# ME4Driver.net
KiCad netlist of a schematic drawn in EasyEDA Pro
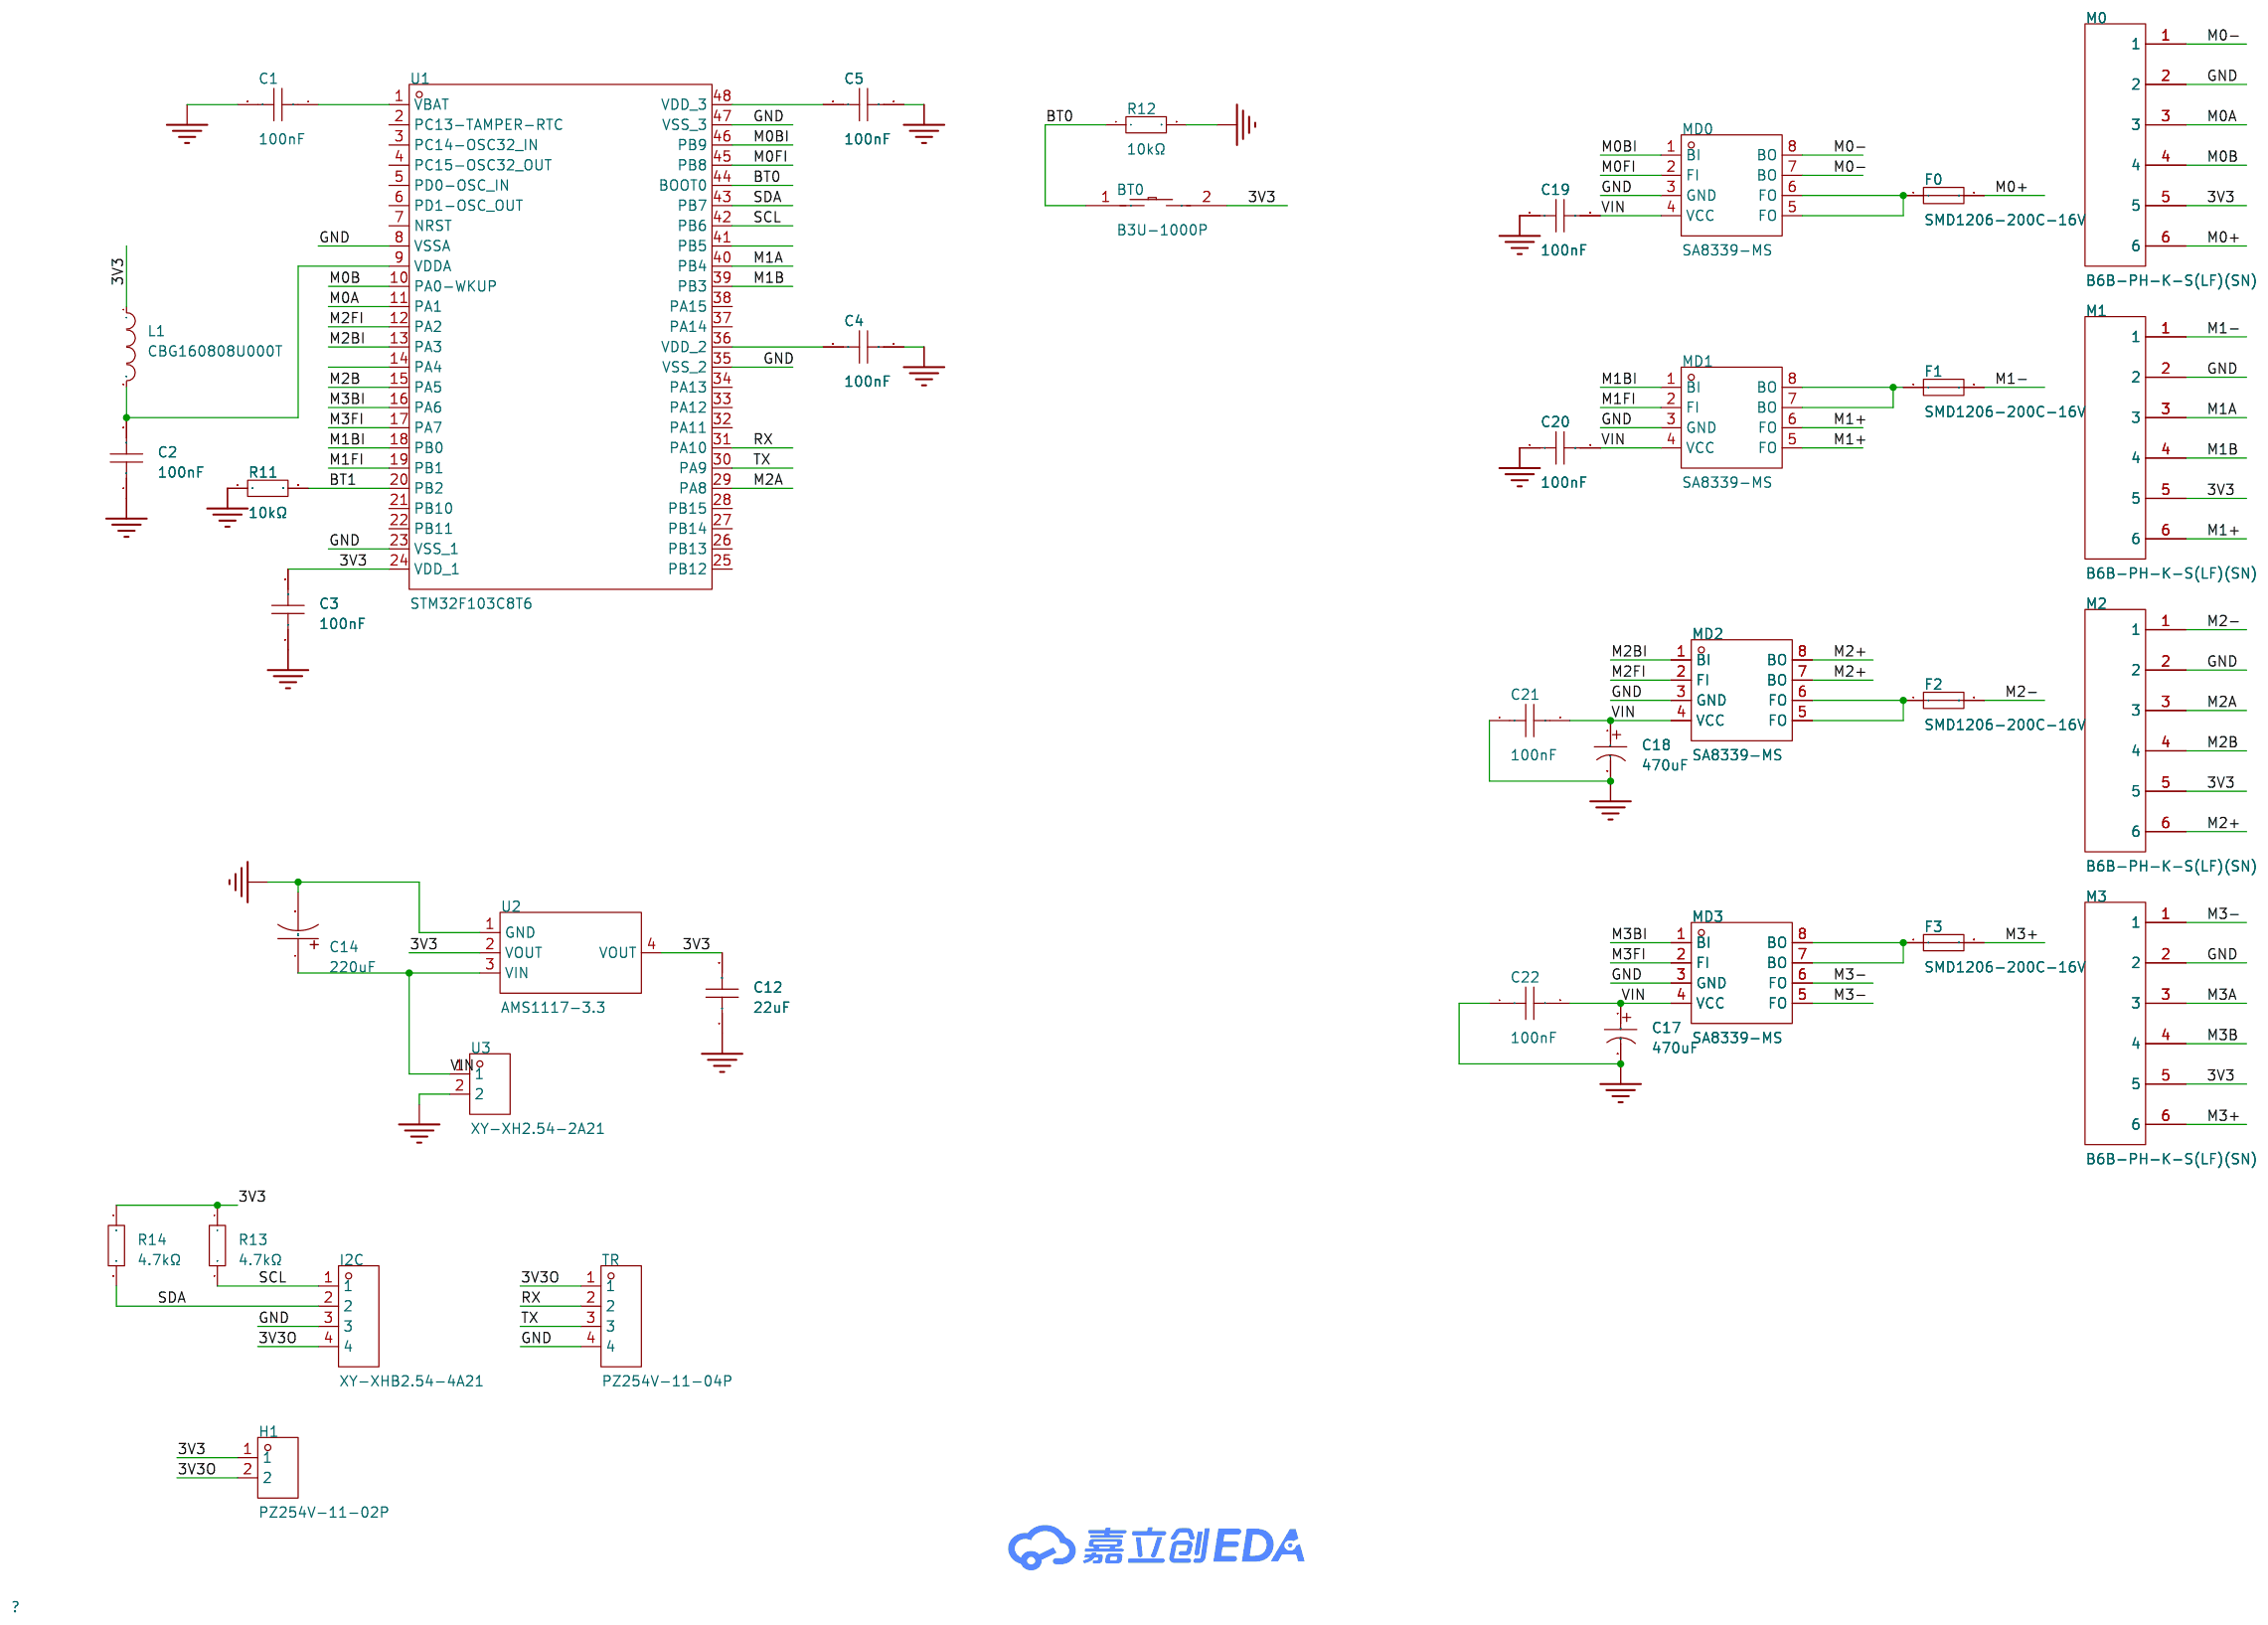
[diagram p0: schematic sheet]

(export (version "E")
  (design (tool "Eeschema 10.0.6"))
  (components
    (comp (ref "BT0")
      (value "B3U-1000P")
      (footprint "easyedapro:KEY-SMD_B3U-1000PM")
      (fields (field (name "Manufacturer") "OMRON(欧姆龙)"))
      (libsource (lib "easyedapro") (part "B3U-1000P"))
    )
    (comp (ref "C1")
      (value "100nF")
      (footprint "easyedapro:C0603")
      (description "容值:100nF;精度:±10%;额定电压:50V;材质(温度系数):X7R;")
      (fields
        (field (name "Manufacturer Part") "CGA0603X7R104K500JT")
        (field (name "Manufacturer") "HRE(芯声)")
      )
      (libsource (lib "easyedapro") (part "CGA0603X7R104K500JT"))
    )
    (comp (ref "C2")
      (value "100nF")
      (footprint "easyedapro:C0603")
      (description "容值:100nF;精度:±10%;额定电压:50V;材质(温度系数):X7R;")
      (fields
        (field (name "Manufacturer Part") "CGA0603X7R104K500JT")
        (field (name "Manufacturer") "HRE(芯声)")
      )
      (libsource (lib "easyedapro") (part "CGA0603X7R104K500JT"))
    )
    (comp (ref "C3")
      (value "100nF")
      (footprint "easyedapro:C0603")
      (description "容值:100nF;精度:±10%;额定电压:50V;材质(温度系数):X7R;")
      (fields
        (field (name "Manufacturer Part") "CGA0603X7R104K500JT")
        (field (name "Manufacturer") "HRE(芯声)")
      )
      (libsource (lib "easyedapro") (part "CGA0603X7R104K500JT"))
    )
    (comp (ref "C4")
      (value "100nF")
      (footprint "easyedapro:C0603")
      (description "容值:100nF;精度:±10%;额定电压:50V;材质(温度系数):X7R;")
      (fields
        (field (name "Manufacturer Part") "CGA0603X7R104K500JT")
        (field (name "Manufacturer") "HRE(芯声)")
      )
      (libsource (lib "easyedapro") (part "CGA0603X7R104K500JT"))
    )
    (comp (ref "C5")
      (value "100nF")
      (footprint "easyedapro:C0603")
      (description "容值:100nF;精度:±10%;额定电压:50V;材质(温度系数):X7R;")
      (fields
        (field (name "Manufacturer Part") "CGA0603X7R104K500JT")
        (field (name "Manufacturer") "HRE(芯声)")
      )
      (libsource (lib "easyedapro") (part "CGA0603X7R104K500JT"))
    )
    (comp (ref "C12")
      (value "22uF")
      (footprint "easyedapro:C0603")
      (description "容值:100nF;精度:±10%;额定电压:50V;材质(温度系数):X7R;")
      (fields (field (name "Manufacturer Part") "TAJA226K010RNJ") (field (name "Manufacturer") "Kyocera AVX"))
      (libsource (lib "easyedapro") (part "CGA0603X7R104K500JT"))
    )
    (comp (ref "C14")
      (value "220uF")
      (footprint "easyedapro:CAP-SMD_BD6.3-L6.6-W6.6-FD")
      (description "容值:220uF;精度:±20%;额定电压:16V;纹波电流:-;等效串联电阻:-;")
      (fields (field (name "Manufacturer Part") "VT1C221M-CRE77") (field (name "Manufacturer") "VT(首科)"))
      (libsource (lib "easyedapro") (part "VT1C221M-CRE77"))
    )
    (comp (ref "C17")
      (value "470uF")
      (footprint "easyedapro:CAP-TH_BD8.0-P3.50-D0.6-FD")
      (description "容值:220uF;精度:±20%;额定电压:35V;纹波电流:-;等效串联电阻:-;")
      (fields (field (name "Manufacturer Part") "KF471M025F115A") (field (name "Manufacturer") "CapXon(丰宾)"))
      (libsource (lib "easyedapro") (part "220uf/35V"))
    )
    (comp (ref "C18")
      (value "470uF")
      (footprint "easyedapro:CAP-TH_BD8.0-P3.50-D0.6-FD")
      (description "容值:220uF;精度:±20%;额定电压:35V;纹波电流:-;等效串联电阻:-;")
      (fields (field (name "Manufacturer Part") "KF471M025F115A") (field (name "Manufacturer") "CapXon(丰宾)"))
      (libsource (lib "easyedapro") (part "220uf/35V"))
    )
    (comp (ref "C19")
      (value "100nF")
      (footprint "easyedapro:C0603")
      (description "容值:100nF;精度:±10%;额定电压:50V;材质(温度系数):X7R;")
      (fields
        (field (name "Manufacturer Part") "CGA0603X7R104K500JT")
        (field (name "Manufacturer") "HRE(芯声)")
      )
      (libsource (lib "easyedapro") (part "CGA0603X7R104K500JT"))
    )
    (comp (ref "C20")
      (value "100nF")
      (footprint "easyedapro:C0603")
      (description "容值:100nF;精度:±10%;额定电压:50V;材质(温度系数):X7R;")
      (fields
        (field (name "Manufacturer Part") "CGA0603X7R104K500JT")
        (field (name "Manufacturer") "HRE(芯声)")
      )
      (libsource (lib "easyedapro") (part "CGA0603X7R104K500JT"))
    )
    (comp (ref "C21")
      (value "100nF")
      (footprint "easyedapro:C0603")
      (description "容值:100nF;精度:±10%;额定电压:50V;材质(温度系数):X7R;")
      (fields
        (field (name "Manufacturer Part") "CGA0603X7R104K500JT")
        (field (name "Manufacturer") "HRE(芯声)")
      )
      (libsource (lib "easyedapro") (part "CGA0603X7R104K500JT"))
    )
    (comp (ref "C22")
      (value "100nF")
      (footprint "easyedapro:C0603")
      (description "容值:100nF;精度:±10%;额定电压:50V;材质(温度系数):X7R;")
      (fields
        (field (name "Manufacturer Part") "CGA0603X7R104K500JT")
        (field (name "Manufacturer") "HRE(芯声)")
      )
      (libsource (lib "easyedapro") (part "CGA0603X7R104K500JT"))
    )
    (comp (ref "F0")
      (value "SMD1206-200C-16V")
      (footprint "easyedapro:F1812")
      (description "最大电压:16V;最大电流:40A;保持电流:3A;跳闸电流:6A;")
      (fields (field (name "Manufacturer") "BNstar(比诺星)"))
      (libsource (lib "easyedapro") (part "BSMD1812-300-16V"))
    )
    (comp (ref "F1")
      (value "SMD1206-200C-16V")
      (footprint "easyedapro:F1812")
      (description "最大电压:16V;最大电流:40A;保持电流:3A;跳闸电流:6A;")
      (fields (field (name "Manufacturer") "BNstar(比诺星)"))
      (libsource (lib "easyedapro") (part "BSMD1812-300-16V"))
    )
    (comp (ref "F2")
      (value "SMD1206-200C-16V")
      (footprint "easyedapro:F1812")
      (description "最大电压:16V;最大电流:40A;保持电流:3A;跳闸电流:6A;")
      (fields (field (name "Manufacturer") "BNstar(比诺星)"))
      (libsource (lib "easyedapro") (part "BSMD1812-300-16V"))
    )
    (comp (ref "F3")
      (value "SMD1206-200C-16V")
      (footprint "easyedapro:F1812")
      (description "最大电压:16V;最大电流:40A;保持电流:3A;跳闸电流:6A;")
      (fields (field (name "Manufacturer") "BNstar(比诺星)"))
      (libsource (lib "easyedapro") (part "BSMD1812-300-16V"))
    )
    (comp (ref "H1")
      (value "PZ254V-11-02P")
      (footprint "easyedapro:HDR-TH_2P-P2.54-V-M")
      (fields (field (name "Manufacturer") "XFCN(兴飞)"))
      (libsource (lib "easyedapro") (part "PZ254V-11-02P"))
    )
    (comp (ref "I2C")
      (value "XY-XHB2.54-4A21")
      (footprint "easyedapro:HDR-TH_4P-P2.50-H-F-W7.3-N")
      (description "插针结构:1x4P;间距:2.54mm;安装方式:弯插;总PIN数:4P;排数:1;每排PIN数:4;行距:2.54mm;额定电流:2A;工作温度范围:-25°C~+85°C;")
      (fields (field (name "Manufacturer") "XYECONN(辛译)"))
      (libsource (lib "easyedapro") (part "XY-XHB2.54-4A21"))
    )
    (comp (ref "L1")
      (value "CBG160808U000T")
      (footprint "easyedapro:L0603")
      (description "标称阻抗@测试频率:0Ω@100MHz;直流电阻(RDC):100mΩ;")
      (fields (field (name "Manufacturer") "FH(风华)"))
      (libsource (lib "easyedapro") (part "CBG160808U000T"))
    )
    (comp (ref "M0")
      (value "B6B-PH-K-S(LF)(SN)")
      (footprint "easyedapro:CONN-TH_B6B-PH-K-S")
      (fields (field (name "Manufacturer") "JST"))
      (libsource (lib "easyedapro") (part "B6B-PH-K-S(LF)(SN)"))
    )
    (comp (ref "M1")
      (value "B6B-PH-K-S(LF)(SN)")
      (footprint "easyedapro:CONN-TH_B6B-PH-K-S")
      (fields (field (name "Manufacturer") "JST"))
      (libsource (lib "easyedapro") (part "B6B-PH-K-S(LF)(SN)"))
    )
    (comp (ref "M2")
      (value "B6B-PH-K-S(LF)(SN)")
      (footprint "easyedapro:CONN-TH_B6B-PH-K-S")
      (fields (field (name "Manufacturer") "JST"))
      (libsource (lib "easyedapro") (part "B6B-PH-K-S(LF)(SN)"))
    )
    (comp (ref "M3")
      (value "B6B-PH-K-S(LF)(SN)")
      (footprint "easyedapro:CONN-TH_B6B-PH-K-S")
      (fields (field (name "Manufacturer") "JST"))
      (libsource (lib "easyedapro") (part "B6B-PH-K-S(LF)(SN)"))
    )
    (comp (ref "MD0")
      (value "SA8339-MS")
      (footprint "easyedapro:SOP-8_L4.9-W3.9-P1.27-LS6.0-BL")
      (fields (field (name "Manufacturer") "MSKSEMI(美森科)"))
      (libsource (lib "easyedapro") (part "SA8339-MS"))
    )
    (comp (ref "MD1")
      (value "SA8339-MS")
      (footprint "easyedapro:SOP-8_L4.9-W3.9-P1.27-LS6.0-BL")
      (fields (field (name "Manufacturer") "MSKSEMI(美森科)"))
      (libsource (lib "easyedapro") (part "SA8339-MS"))
    )
    (comp (ref "MD2")
      (value "SA8339-MS")
      (footprint "easyedapro:SOP-8_L4.9-W3.9-P1.27-LS6.0-BL")
      (fields (field (name "Manufacturer") "MSKSEMI(美森科)"))
      (libsource (lib "easyedapro") (part "SA8339-MS"))
    )
    (comp (ref "MD3")
      (value "SA8339-MS")
      (footprint "easyedapro:SOP-8_L4.9-W3.9-P1.27-LS6.0-BL")
      (fields (field (name "Manufacturer") "MSKSEMI(美森科)"))
      (libsource (lib "easyedapro") (part "SA8339-MS"))
    )
    (comp (ref "R11")
      (value "10kΩ")
      (fields
        (field (name "Manufacturer Part") "0603WAF1002T5E")
        (field (name "Manufacturer") "UNI-ROYAL(厚声)")
      )
      (libsource (lib "easyedapro") (part "电阻"))
    )
    (comp (ref "R12")
      (value "10kΩ")
      (fields
        (field (name "Manufacturer Part") "0603WAF1002T5E")
        (field (name "Manufacturer") "UNI-ROYAL(厚声)")
      )
      (libsource (lib "easyedapro") (part "电阻"))
    )
    (comp (ref "R13")
      (value "4.7kΩ")
      (footprint "easyedapro:R1206")
      (description "电阻类型:厚膜电阻;阻值:4.7kΩ;精度:±1%;功率:250mW;最大工作电压:200V;温度系数:±100ppm/°C;")
      (fields
        (field (name "Manufacturer Part") "1206W4F4701T5E")
        (field (name "Manufacturer") "UNI-ROYAL(厚声)")
      )
      (libsource (lib "easyedapro") (part "1206W4F4701T5E"))
    )
    (comp (ref "R14")
      (value "4.7kΩ")
      (footprint "easyedapro:R1206")
      (description "电阻类型:厚膜电阻;阻值:4.7kΩ;精度:±1%;功率:250mW;最大工作电压:200V;温度系数:±100ppm/°C;")
      (fields
        (field (name "Manufacturer Part") "1206W4F4701T5E")
        (field (name "Manufacturer") "UNI-ROYAL(厚声)")
      )
      (libsource (lib "easyedapro") (part "1206W4F4701T5E"))
    )
    (comp (ref "TR")
      (value "PZ254V-11-04P")
      (footprint "easyedapro:HDR-TH_4P-P2.54-V-M")
      (fields (field (name "Manufacturer") "XFCN(兴飞)"))
      (libsource (lib "easyedapro") (part "PZ254V-11-04P_C2691448"))
    )
    (comp (ref "U1")
      (value "STM32F103C8T6")
      (footprint "easyedapro:LQFP-48_L7.0-W7.0-P0.50-LS9.0-BL")
      (description "CPU内核:ARM-M3;CPU最大主频:72MHz;应用领域:-;")
      (fields (field (name "Manufacturer") "ST(意法半导体)"))
      (libsource (lib "easyedapro") (part "STM32F103C8T6"))
    )
    (comp (ref "U2")
      (value "AMS1117-3.3")
      (footprint "easyedapro:SOT-223-3_L6.5-W3.4-P2.30-LS7.0-BR")
      (description "输出类型:固定;工作电压:-;输出电压:3.3V;输出电流:1A;电源纹波抑制比(PSRR):72dB@(120Hz);输出极性:正极;")
      (fields (field (name "Manufacturer") "AMS"))
      (libsource (lib "easyedapro") (part "AMS1117-3.3"))
    )
    (comp (ref "U3")
      (value "XY-XH2.54-2A21")
      (footprint "easyedapro:HDR-TH_2P-P2.50_XY-XH2.54-2A21")
      (description "插针结构:1x2P;间距:2.54mm;安装方式:弯插;总PIN数:2P;排数:1;每排PIN数:2;行距:2.54mm;额定电流:3A;工作温度范围:-25°C~+85°C;")
      (fields (field (name "Manufacturer") "XYECONN(辛译)"))
      (libsource (lib "easyedapro") (part "XY-XH2.54-2A21"))
    )
  )
  (nets
    (net (code "1") (name "/3V3") (class "Default")
      (node (ref "BT0") (pin "2") (pinfunction "2_2") (pintype "unspecified"))
      (node (ref "C12") (pin "2") (pinfunction "2_2") (pintype "unspecified"))
      (node (ref "C3") (pin "2") (pinfunction "2_2") (pintype "unspecified"))
      (node (ref "H1") (pin "1") (pinfunction "1_1") (pintype "unspecified"))
      (node (ref "L1") (pin "1") (pinfunction "1_1") (pintype "unspecified"))
      (node (ref "M0") (pin "5") (pinfunction "5_5") (pintype "input"))
      (node (ref "M1") (pin "5") (pinfunction "5_5") (pintype "input"))
      (node (ref "M2") (pin "5") (pinfunction "5_5") (pintype "input"))
      (node (ref "M3") (pin "5") (pinfunction "5_5") (pintype "input"))
      (node (ref "R13") (pin "1") (pinfunction "1_1") (pintype "input"))
      (node (ref "R14") (pin "1") (pinfunction "1_1") (pintype "input"))
      (node (ref "U1") (pin "24") (pinfunction "VDD_1_24") (pintype "unspecified"))
      (node (ref "U2") (pin "2") (pinfunction "VOUT_2") (pintype "unspecified"))
      (node (ref "U2") (pin "4") (pinfunction "VOUT_4") (pintype "unspecified"))
    )
    (net (code "2") (name "/3V3O") (class "Default")
      (node (ref "H1") (pin "2") (pinfunction "2_2") (pintype "unspecified"))
      (node (ref "I2C") (pin "4") (pinfunction "4_4") (pintype "unspecified"))
      (node (ref "TR") (pin "1") (pinfunction "1_1") (pintype "unspecified"))
    )
    (net (code "3") (name "/BT0") (class "Default")
      (node (ref "BT0") (pin "1") (pinfunction "1_1") (pintype "unspecified"))
      (node (ref "R12") (pin "1") (pinfunction "1_1") (pintype "input"))
      (node (ref "U1") (pin "44") (pinfunction "BOOT0_44") (pintype "unspecified"))
    )
    (net (code "4") (name "/BT1") (class "Default")
      (node (ref "R11") (pin "2") (pinfunction "2_2") (pintype "input"))
      (node (ref "U1") (pin "20") (pinfunction "PB2_20") (pintype "unspecified"))
    )
    (net (code "5") (name "/M0+") (class "Default")
      (node (ref "F0") (pin "2") (pinfunction "2_2") (pintype "unspecified"))
      (node (ref "M0") (pin "6") (pinfunction "6_6") (pintype "input"))
    )
    (net (code "6") (name "/M0-") (class "Default")
      (node (ref "M0") (pin "1") (pinfunction "1_1") (pintype "input"))
      (node (ref "MD0") (pin "7") (pinfunction "BO_7") (pintype "unspecified"))
      (node (ref "MD0") (pin "8") (pinfunction "BO_8") (pintype "unspecified"))
    )
    (net (code "7") (name "/M0A") (class "Default")
      (node (ref "M0") (pin "3") (pinfunction "3_3") (pintype "input"))
      (node (ref "U1") (pin "11") (pinfunction "PA1_11") (pintype "unspecified"))
    )
    (net (code "8") (name "/M0B") (class "Default")
      (node (ref "M0") (pin "4") (pinfunction "4_4") (pintype "input"))
      (node (ref "U1") (pin "10") (pinfunction "PA0-WKUP_10") (pintype "unspecified"))
    )
    (net (code "9") (name "/M0BI") (class "Default")
      (node (ref "MD0") (pin "1") (pinfunction "BI_1") (pintype "unspecified"))
      (node (ref "U1") (pin "46") (pinfunction "PB9_46") (pintype "unspecified"))
    )
    (net (code "10") (name "/M0FI") (class "Default")
      (node (ref "MD0") (pin "2") (pinfunction "FI_2") (pintype "unspecified"))
      (node (ref "U1") (pin "45") (pinfunction "PB8_45") (pintype "unspecified"))
    )
    (net (code "11") (name "/M1+") (class "Default")
      (node (ref "M1") (pin "6") (pinfunction "6_6") (pintype "input"))
      (node (ref "MD1") (pin "5") (pinfunction "FO_5") (pintype "unspecified"))
      (node (ref "MD1") (pin "6") (pinfunction "FO_6") (pintype "unspecified"))
    )
    (net (code "12") (name "/M1-") (class "Default")
      (node (ref "F1") (pin "2") (pinfunction "2_2") (pintype "unspecified"))
      (node (ref "M1") (pin "1") (pinfunction "1_1") (pintype "input"))
    )
    (net (code "13") (name "/M1A") (class "Default")
      (node (ref "M1") (pin "3") (pinfunction "3_3") (pintype "input"))
      (node (ref "U1") (pin "40") (pinfunction "PB4_40") (pintype "unspecified"))
    )
    (net (code "14") (name "/M1B") (class "Default")
      (node (ref "M1") (pin "4") (pinfunction "4_4") (pintype "input"))
      (node (ref "U1") (pin "39") (pinfunction "PB3_39") (pintype "unspecified"))
    )
    (net (code "15") (name "/M1BI") (class "Default")
      (node (ref "MD1") (pin "1") (pinfunction "BI_1") (pintype "unspecified"))
      (node (ref "U1") (pin "18") (pinfunction "PB0_18") (pintype "unspecified"))
    )
    (net (code "16") (name "/M1FI") (class "Default")
      (node (ref "MD1") (pin "2") (pinfunction "FI_2") (pintype "unspecified"))
      (node (ref "U1") (pin "19") (pinfunction "PB1_19") (pintype "unspecified"))
    )
    (net (code "17") (name "/M2+") (class "Default")
      (node (ref "M2") (pin "6") (pinfunction "6_6") (pintype "input"))
      (node (ref "MD2") (pin "7") (pinfunction "BO_7") (pintype "unspecified"))
      (node (ref "MD2") (pin "8") (pinfunction "BO_8") (pintype "unspecified"))
    )
    (net (code "18") (name "/M2-") (class "Default")
      (node (ref "F2") (pin "2") (pinfunction "2_2") (pintype "unspecified"))
      (node (ref "M2") (pin "1") (pinfunction "1_1") (pintype "input"))
    )
    (net (code "19") (name "/M2A") (class "Default")
      (node (ref "M2") (pin "3") (pinfunction "3_3") (pintype "input"))
      (node (ref "U1") (pin "29") (pinfunction "PA8_29") (pintype "unspecified"))
    )
    (net (code "20") (name "/M2B") (class "Default")
      (node (ref "M2") (pin "4") (pinfunction "4_4") (pintype "input"))
      (node (ref "U1") (pin "15") (pinfunction "PA5_15") (pintype "unspecified"))
    )
    (net (code "21") (name "/M2BI") (class "Default")
      (node (ref "MD2") (pin "1") (pinfunction "BI_1") (pintype "unspecified"))
      (node (ref "U1") (pin "13") (pinfunction "PA3_13") (pintype "unspecified"))
    )
    (net (code "22") (name "/M2FI") (class "Default")
      (node (ref "MD2") (pin "2") (pinfunction "FI_2") (pintype "unspecified"))
      (node (ref "U1") (pin "12") (pinfunction "PA2_12") (pintype "unspecified"))
    )
    (net (code "23") (name "/M3+") (class "Default")
      (node (ref "F3") (pin "2") (pinfunction "2_2") (pintype "unspecified"))
      (node (ref "M3") (pin "6") (pinfunction "6_6") (pintype "input"))
    )
    (net (code "24") (name "/M3-") (class "Default")
      (node (ref "M3") (pin "1") (pinfunction "1_1") (pintype "input"))
      (node (ref "MD3") (pin "5") (pinfunction "FO_5") (pintype "unspecified"))
      (node (ref "MD3") (pin "6") (pinfunction "FO_6") (pintype "unspecified"))
    )
    (net (code "25") (name "/M3A") (class "Default")
      (node (ref "M3") (pin "3") (pinfunction "3_3") (pintype "input"))
    )
    (net (code "26") (name "/M3B") (class "Default")
      (node (ref "M3") (pin "4") (pinfunction "4_4") (pintype "input"))
    )
    (net (code "27") (name "/M3BI") (class "Default")
      (node (ref "MD3") (pin "1") (pinfunction "BI_1") (pintype "unspecified"))
      (node (ref "U1") (pin "16") (pinfunction "PA6_16") (pintype "unspecified"))
    )
    (net (code "28") (name "/M3FI") (class "Default")
      (node (ref "MD3") (pin "2") (pinfunction "FI_2") (pintype "unspecified"))
      (node (ref "U1") (pin "17") (pinfunction "PA7_17") (pintype "unspecified"))
    )
    (net (code "29") (name "/RX") (class "Default")
      (node (ref "TR") (pin "2") (pinfunction "2_2") (pintype "unspecified"))
      (node (ref "U1") (pin "31") (pinfunction "PA10_31") (pintype "unspecified"))
    )
    (net (code "30") (name "/SCL") (class "Default")
      (node (ref "I2C") (pin "1") (pinfunction "1_1") (pintype "unspecified"))
      (node (ref "R13") (pin "2") (pinfunction "2_2") (pintype "input"))
      (node (ref "U1") (pin "42") (pinfunction "PB6_42") (pintype "unspecified"))
    )
    (net (code "31") (name "/SDA") (class "Default")
      (node (ref "I2C") (pin "2") (pinfunction "2_2") (pintype "unspecified"))
      (node (ref "R14") (pin "2") (pinfunction "2_2") (pintype "input"))
      (node (ref "U1") (pin "43") (pinfunction "PB7_43") (pintype "unspecified"))
    )
    (net (code "32") (name "/TX") (class "Default")
      (node (ref "TR") (pin "3") (pinfunction "3_3") (pintype "unspecified"))
      (node (ref "U1") (pin "30") (pinfunction "PA9_30") (pintype "unspecified"))
    )
    (net (code "33") (name "/VIN") (class "Default")
      (node (ref "C14") (pin "1") (pinfunction "1_1") (pintype "unspecified"))
      (node (ref "C17") (pin "1") (pinfunction "1_1") (pintype "input"))
      (node (ref "C18") (pin "1") (pinfunction "1_1") (pintype "input"))
      (node (ref "C19") (pin "2") (pinfunction "2_2") (pintype "unspecified"))
      (node (ref "C20") (pin "2") (pinfunction "2_2") (pintype "unspecified"))
      (node (ref "C21") (pin "2") (pinfunction "2_2") (pintype "unspecified"))
      (node (ref "C22") (pin "2") (pinfunction "2_2") (pintype "unspecified"))
      (node (ref "MD0") (pin "4") (pinfunction "VCC_4") (pintype "unspecified"))
      (node (ref "MD1") (pin "4") (pinfunction "VCC_4") (pintype "unspecified"))
      (node (ref "MD2") (pin "4") (pinfunction "VCC_4") (pintype "unspecified"))
      (node (ref "MD3") (pin "4") (pinfunction "VCC_4") (pintype "unspecified"))
      (node (ref "U2") (pin "3") (pinfunction "VIN_3") (pintype "unspecified"))
      (node (ref "U3") (pin "1") (pinfunction "1_1") (pintype "unspecified"))
    )
    (net (code "34") (name "GND") (class "Default")
      (node (ref "C1") (pin "2") (pinfunction "2_2") (pintype "unspecified"))
      (node (ref "C12") (pin "1") (pinfunction "1_1") (pintype "unspecified"))
      (node (ref "C14") (pin "2") (pinfunction "2_2") (pintype "unspecified"))
      (node (ref "C17") (pin "2") (pinfunction "2_2") (pintype "input"))
      (node (ref "C18") (pin "2") (pinfunction "2_2") (pintype "input"))
      (node (ref "C19") (pin "1") (pinfunction "1_1") (pintype "unspecified"))
      (node (ref "C2") (pin "1") (pinfunction "1_1") (pintype "unspecified"))
      (node (ref "C20") (pin "1") (pinfunction "1_1") (pintype "unspecified"))
      (node (ref "C21") (pin "1") (pinfunction "1_1") (pintype "unspecified"))
      (node (ref "C22") (pin "1") (pinfunction "1_1") (pintype "unspecified"))
      (node (ref "C3") (pin "1") (pinfunction "1_1") (pintype "unspecified"))
      (node (ref "C4") (pin "1") (pinfunction "1_1") (pintype "unspecified"))
      (node (ref "C5") (pin "1") (pinfunction "1_1") (pintype "unspecified"))
      (node (ref "I2C") (pin "3") (pinfunction "3_3") (pintype "unspecified"))
      (node (ref "M0") (pin "2") (pinfunction "2_2") (pintype "input"))
      (node (ref "M1") (pin "2") (pinfunction "2_2") (pintype "input"))
      (node (ref "M2") (pin "2") (pinfunction "2_2") (pintype "input"))
      (node (ref "M3") (pin "2") (pinfunction "2_2") (pintype "input"))
      (node (ref "MD0") (pin "3") (pinfunction "GND_3") (pintype "unspecified"))
      (node (ref "MD1") (pin "3") (pinfunction "GND_3") (pintype "unspecified"))
      (node (ref "MD2") (pin "3") (pinfunction "GND_3") (pintype "unspecified"))
      (node (ref "MD3") (pin "3") (pinfunction "GND_3") (pintype "unspecified"))
      (node (ref "R11") (pin "1") (pinfunction "1_1") (pintype "input"))
      (node (ref "R12") (pin "2") (pinfunction "2_2") (pintype "input"))
      (node (ref "TR") (pin "4") (pinfunction "4_4") (pintype "unspecified"))
      (node (ref "U1") (pin "23") (pinfunction "VSS_1_23") (pintype "unspecified"))
      (node (ref "U1") (pin "35") (pinfunction "VSS_2_35") (pintype "unspecified"))
      (node (ref "U1") (pin "47") (pinfunction "VSS_3_47") (pintype "unspecified"))
      (node (ref "U1") (pin "8") (pinfunction "VSSA_8") (pintype "unspecified"))
      (node (ref "U2") (pin "1") (pinfunction "GND_1") (pintype "unspecified"))
      (node (ref "U3") (pin "2") (pinfunction "2_2") (pintype "unspecified"))
    )
    (net (code "35") (name "Net-(F0-Pad1)") (class "Default")
      (node (ref "F0") (pin "1") (pinfunction "1_1") (pintype "unspecified"))
      (node (ref "MD0") (pin "5") (pinfunction "FO_5") (pintype "unspecified"))
      (node (ref "MD0") (pin "6") (pinfunction "FO_6") (pintype "unspecified"))
    )
    (net (code "36") (name "Net-(F1-Pad1)") (class "Default")
      (node (ref "F1") (pin "1") (pinfunction "1_1") (pintype "unspecified"))
      (node (ref "MD1") (pin "7") (pinfunction "BO_7") (pintype "unspecified"))
      (node (ref "MD1") (pin "8") (pinfunction "BO_8") (pintype "unspecified"))
    )
    (net (code "37") (name "Net-(F2-Pad1)") (class "Default")
      (node (ref "F2") (pin "1") (pinfunction "1_1") (pintype "unspecified"))
      (node (ref "MD2") (pin "5") (pinfunction "FO_5") (pintype "unspecified"))
      (node (ref "MD2") (pin "6") (pinfunction "FO_6") (pintype "unspecified"))
    )
    (net (code "38") (name "Net-(F3-Pad1)") (class "Default")
      (node (ref "F3") (pin "1") (pinfunction "1_1") (pintype "unspecified"))
      (node (ref "MD3") (pin "7") (pinfunction "BO_7") (pintype "unspecified"))
      (node (ref "MD3") (pin "8") (pinfunction "BO_8") (pintype "unspecified"))
    )
    (net (code "39") (name "Net-(U1-VBAT)") (class "Default")
      (node (ref "C1") (pin "1") (pinfunction "1_1") (pintype "unspecified"))
      (node (ref "U1") (pin "1") (pinfunction "VBAT_1") (pintype "unspecified"))
    )
    (net (code "40") (name "Net-(U1-VDDA)") (class "Default")
      (node (ref "C2") (pin "2") (pinfunction "2_2") (pintype "unspecified"))
      (node (ref "L1") (pin "2") (pinfunction "2_2") (pintype "unspecified"))
      (node (ref "U1") (pin "9") (pinfunction "VDDA_9") (pintype "unspecified"))
    )
    (net (code "41") (name "Net-(U1-VDD_2)") (class "Default")
      (node (ref "C4") (pin "2") (pinfunction "2_2") (pintype "unspecified"))
      (node (ref "U1") (pin "36") (pinfunction "VDD_2_36") (pintype "unspecified"))
    )
    (net (code "42") (name "Net-(U1-VDD_3)") (class "Default")
      (node (ref "C5") (pin "2") (pinfunction "2_2") (pintype "unspecified"))
      (node (ref "U1") (pin "48") (pinfunction "VDD_3_48") (pintype "unspecified"))
    )
    (net (code "43") (name "unconnected-(U1-NRST-Pad7)") (class "Default")
      (node (ref "U1") (pin "7") (pinfunction "NRST_7") (pintype "unspecified"))
    )
    (net (code "44") (name "unconnected-(U1-PA4-Pad14)") (class "Default")
      (node (ref "U1") (pin "14") (pinfunction "PA4_14") (pintype "unspecified"))
    )
    (net (code "45") (name "unconnected-(U1-PA11-Pad32)") (class "Default")
      (node (ref "U1") (pin "32") (pinfunction "PA11_32") (pintype "unspecified"))
    )
    (net (code "46") (name "unconnected-(U1-PA12-Pad33)") (class "Default")
      (node (ref "U1") (pin "33") (pinfunction "PA12_33") (pintype "unspecified"))
    )
    (net (code "47") (name "unconnected-(U1-PA13-Pad34)") (class "Default")
      (node (ref "U1") (pin "34") (pinfunction "PA13_34") (pintype "unspecified"))
    )
    (net (code "48") (name "unconnected-(U1-PA14-Pad37)") (class "Default")
      (node (ref "U1") (pin "37") (pinfunction "PA14_37") (pintype "unspecified"))
    )
    (net (code "49") (name "unconnected-(U1-PA15-Pad38)") (class "Default")
      (node (ref "U1") (pin "38") (pinfunction "PA15_38") (pintype "unspecified"))
    )
    (net (code "50") (name "unconnected-(U1-PB5-Pad41)") (class "Default")
      (node (ref "U1") (pin "41") (pinfunction "PB5_41") (pintype "unspecified"))
    )
    (net (code "51") (name "unconnected-(U1-PB10-Pad21)") (class "Default")
      (node (ref "U1") (pin "21") (pinfunction "PB10_21") (pintype "unspecified"))
    )
    (net (code "52") (name "unconnected-(U1-PB11-Pad22)") (class "Default")
      (node (ref "U1") (pin "22") (pinfunction "PB11_22") (pintype "unspecified"))
    )
    (net (code "53") (name "unconnected-(U1-PB12-Pad25)") (class "Default")
      (node (ref "U1") (pin "25") (pinfunction "PB12_25") (pintype "unspecified"))
    )
    (net (code "54") (name "unconnected-(U1-PB13-Pad26)") (class "Default")
      (node (ref "U1") (pin "26") (pinfunction "PB13_26") (pintype "unspecified"))
    )
    (net (code "55") (name "unconnected-(U1-PB14-Pad27)") (class "Default")
      (node (ref "U1") (pin "27") (pinfunction "PB14_27") (pintype "unspecified"))
    )
    (net (code "56") (name "unconnected-(U1-PB15-Pad28)") (class "Default")
      (node (ref "U1") (pin "28") (pinfunction "PB15_28") (pintype "unspecified"))
    )
    (net (code "57") (name "unconnected-(U1-PC13-TAMPER-RTC-Pad2)") (class "Default")
      (node (ref "U1") (pin "2") (pinfunction "PC13-TAMPER-RTC_2") (pintype "unspecified"))
    )
    (net (code "58") (name "unconnected-(U1-PC14-OSC32_IN-Pad3)") (class "Default")
      (node (ref "U1") (pin "3") (pinfunction "PC14-OSC32_IN_3") (pintype "unspecified"))
    )
    (net (code "59") (name "unconnected-(U1-PC15-OSC32_OUT-Pad4)") (class "Default")
      (node (ref "U1") (pin "4") (pinfunction "PC15-OSC32_OUT_4") (pintype "unspecified"))
    )
    (net (code "60") (name "unconnected-(U1-PD0-OSC_IN-Pad5)") (class "Default")
      (node (ref "U1") (pin "5") (pinfunction "PD0-OSC_IN_5") (pintype "unspecified"))
    )
    (net (code "61") (name "unconnected-(U1-PD1-OSC_OUT-Pad6)") (class "Default")
      (node (ref "U1") (pin "6") (pinfunction "PD1-OSC_OUT_6") (pintype "unspecified"))
    )
  )
)
